# main_module_0_1.net
KiCad netlist of a schematic drawn in EAGLE
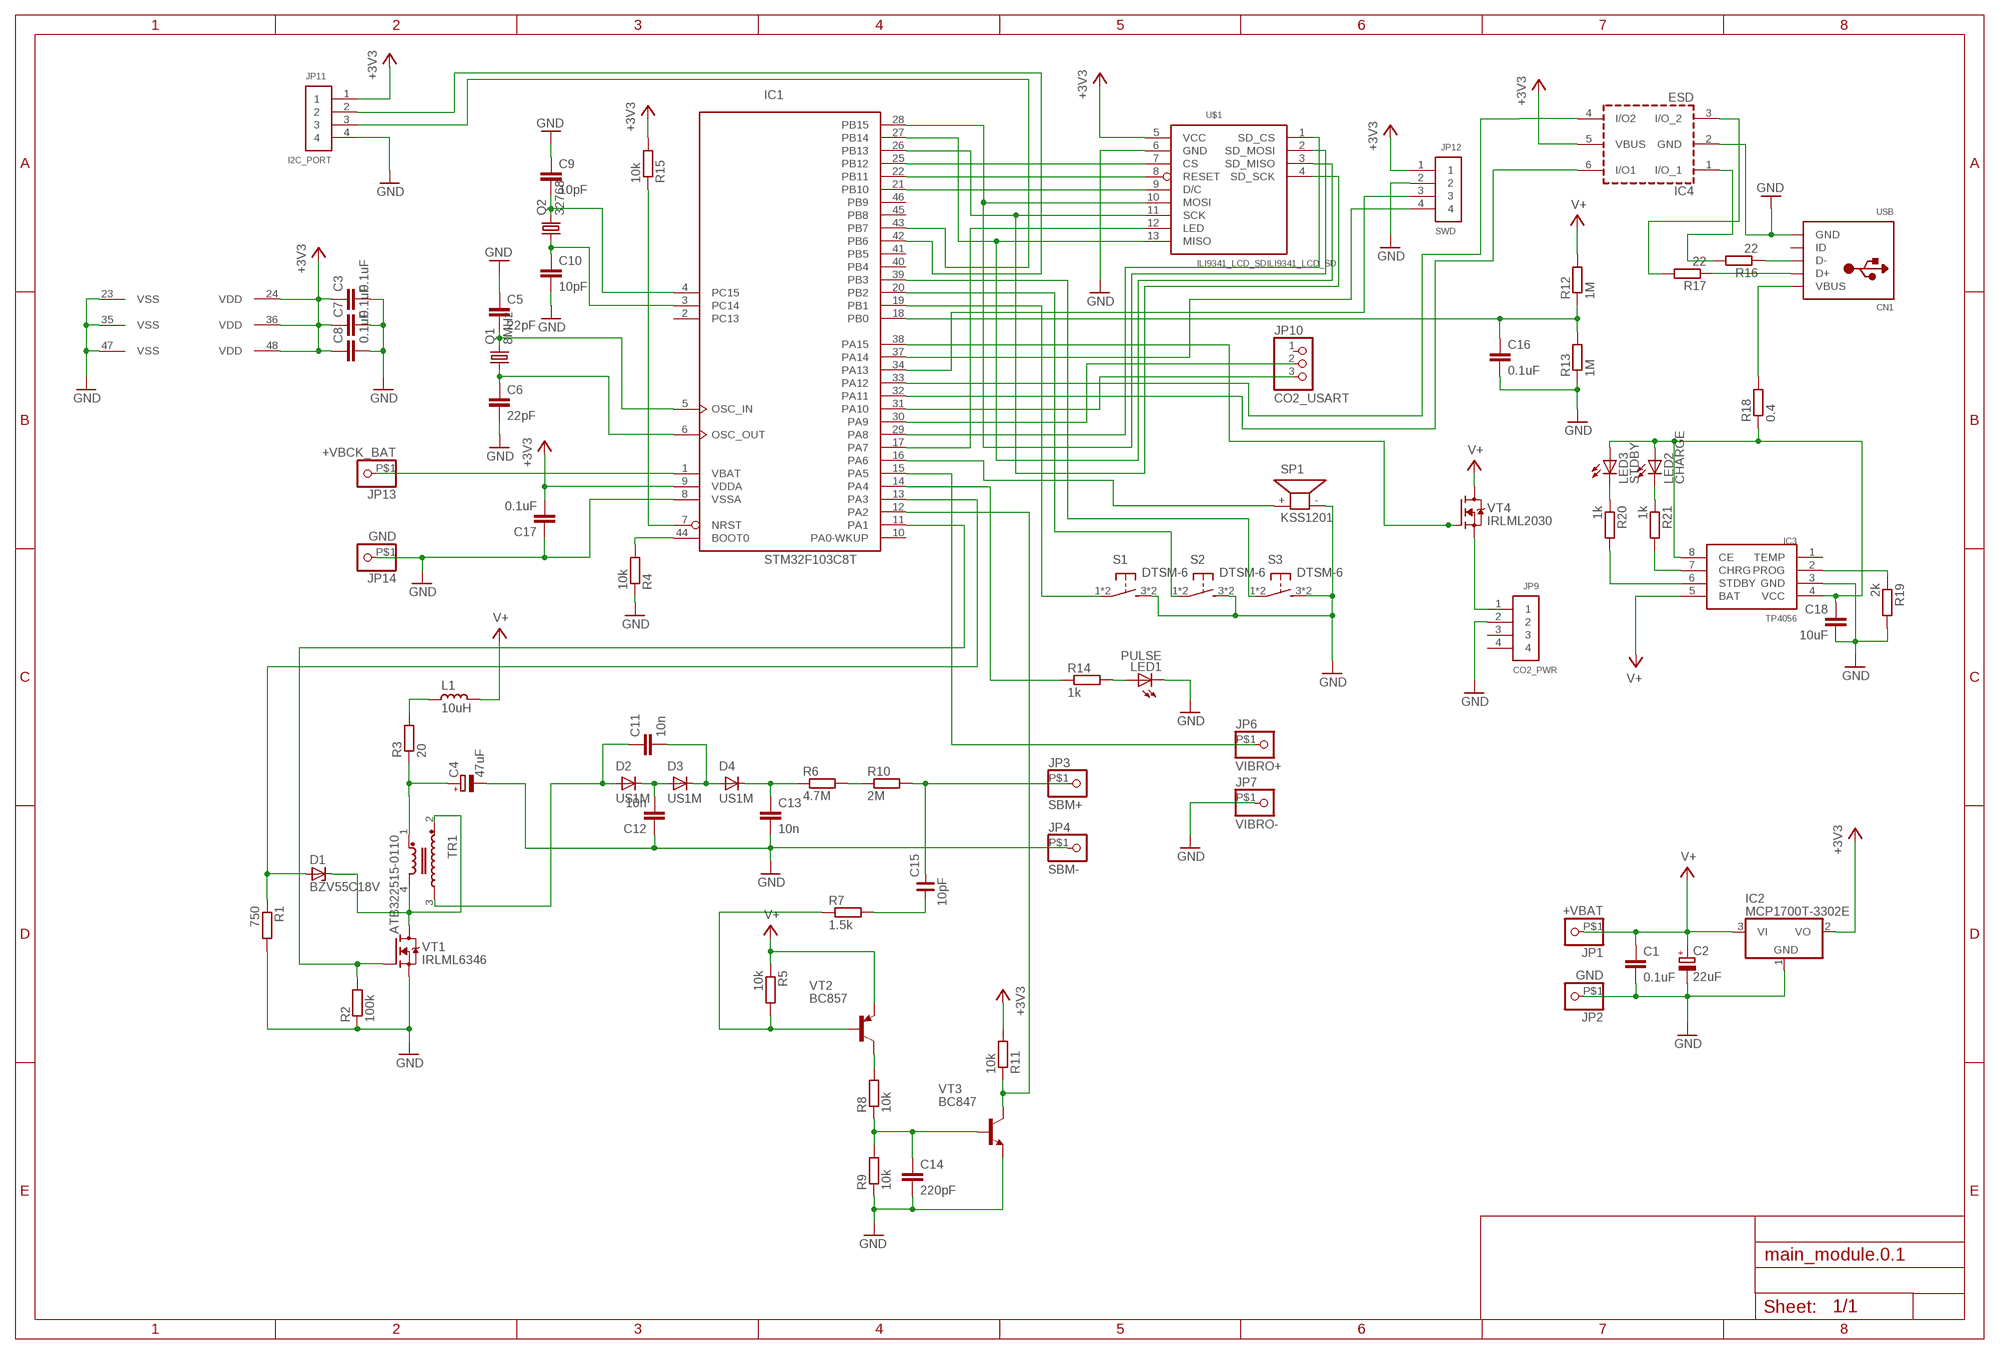
[diagram p0: schematic, sheet 1]

(export (version "E")
  (design (tool "Eeschema 10.0.6"))
  (components
    (comp (ref "C1")
      (value "0.1uF")
      (footprint "eagle-import:C0805")
      (libsource (lib "eagle-import") (part "C-EUC0805"))
    )
    (comp (ref "C2")
      (value "22uF")
      (footprint "eagle-import:C_6032-28R")
      (libsource (lib "eagle-import") (part "CPOL-EUC/6032-28R"))
    )
    (comp (ref "C3")
      (value "0.1uF")
      (footprint "eagle-import:C0805")
      (libsource (lib "eagle-import") (part "C-EUC0805"))
    )
    (comp (ref "C4")
      (value "47uF")
      (footprint "eagle-import:C_6032-28R")
      (libsource (lib "eagle-import") (part "CPOL-EUC/6032-28R"))
    )
    (comp (ref "C5")
      (value "22pF")
      (footprint "eagle-import:C0805")
      (libsource (lib "eagle-import") (part "C-EUC0805"))
    )
    (comp (ref "C6")
      (value "22pF")
      (footprint "eagle-import:C0805")
      (libsource (lib "eagle-import") (part "C-EUC0805"))
    )
    (comp (ref "C7")
      (value "0.1uF")
      (footprint "eagle-import:C0805")
      (libsource (lib "eagle-import") (part "C-EUC0805"))
    )
    (comp (ref "C8")
      (value "0.1uF")
      (footprint "eagle-import:C0805")
      (libsource (lib "eagle-import") (part "C-EUC0805"))
    )
    (comp (ref "C9")
      (value "10pF")
      (footprint "eagle-import:C0805")
      (libsource (lib "eagle-import") (part "C-EUC0805"))
    )
    (comp (ref "C10")
      (value "10pF")
      (footprint "eagle-import:C0805")
      (libsource (lib "eagle-import") (part "C-EUC0805"))
    )
    (comp (ref "C11")
      (value "10n")
      (footprint "eagle-import:C1206")
      (libsource (lib "eagle-import") (part "C-EUC1206"))
    )
    (comp (ref "C12")
      (value "10n")
      (footprint "eagle-import:C1206")
      (libsource (lib "eagle-import") (part "C-EUC1206"))
    )
    (comp (ref "C13")
      (value "10n")
      (footprint "eagle-import:C1206")
      (libsource (lib "eagle-import") (part "C-EUC1206"))
    )
    (comp (ref "C14")
      (value "220pF")
      (footprint "eagle-import:C0805")
      (libsource (lib "eagle-import") (part "C-EUC0805"))
    )
    (comp (ref "C15")
      (value "10pF")
      (footprint "eagle-import:C1206")
      (libsource (lib "eagle-import") (part "C_1206"))
    )
    (comp (ref "C16")
      (value "0.1uF")
      (footprint "eagle-import:C0805")
      (libsource (lib "eagle-import") (part "C-EUC0805"))
    )
    (comp (ref "C17")
      (value "0.1uF")
      (footprint "eagle-import:C0805")
      (libsource (lib "eagle-import") (part "C-EUC0805"))
    )
    (comp (ref "C18")
      (value "10uF")
      (footprint "eagle-import:C0805")
      (libsource (lib "eagle-import") (part "C-EUC0805"))
    )
    (comp (ref "CN1")
      (value "USB")
      (footprint "eagle-import:USB-MINIB")
      (libsource (lib "eagle-import") (part "USBMINIB"))
    )
    (comp (ref "D1")
      (value "BZV55C18V")
      (footprint "eagle-import:SOD80C")
      (libsource (lib "eagle-import") (part "ZENER-DIODESOD80C"))
    )
    (comp (ref "D2")
      (value "US1M")
      (footprint "eagle-import:SMA-DO214AC")
      (libsource (lib "eagle-import") (part "GF1"))
    )
    (comp (ref "D3")
      (value "US1M")
      (footprint "eagle-import:SMA-DO214AC")
      (libsource (lib "eagle-import") (part "GF1"))
    )
    (comp (ref "D4")
      (value "US1M")
      (footprint "eagle-import:SMA-DO214AC")
      (libsource (lib "eagle-import") (part "GF1"))
    )
    (comp (ref "IC1")
      (value "STM32F103C8T")
      (footprint "eagle-import:LQFP48")
      (libsource (lib "eagle-import") (part "STM32F103CT8"))
    )
    (comp (ref "IC2")
      (value "MCP1700T-3302E")
      (footprint "eagle-import:SOT23")
      (libsource (lib "eagle-import") (part "MCP1703CB"))
    )
    (comp (ref "IC3")
      (value "TP4056")
      (footprint "eagle-import:SOP-8")
      (libsource (lib "eagle-import") (part "TP4056"))
    )
    (comp (ref "IC4")
      (value "ESD")
      (footprint "eagle-import:SOT-23-6L")
      (libsource (lib "eagle-import") (part "USBLC6-2SC6"))
    )
    (comp (ref "JP1")
      (value "+VBAT")
      (footprint "eagle-import:1X1-BIGPOGO")
      (libsource (lib "eagle-import") (part "PINHD-1X1-BIGPOGO"))
    )
    (comp (ref "JP2")
      (value "GND")
      (footprint "eagle-import:1X1-BIGPOGO")
      (libsource (lib "eagle-import") (part "PINHD-1X1-BIGPOGO"))
    )
    (comp (ref "JP3")
      (value "SBM+")
      (footprint "eagle-import:1X1-BIGPOGO")
      (libsource (lib "eagle-import") (part "PINHD-1X1-BIGPOGO"))
    )
    (comp (ref "JP4")
      (value "SBM-")
      (footprint "eagle-import:1X1-BIGPOGO")
      (libsource (lib "eagle-import") (part "PINHD-1X1-BIGPOGO"))
    )
    (comp (ref "JP6")
      (value "VIBRO+")
      (footprint "eagle-import:1X1-BIGPOGO")
      (libsource (lib "eagle-import") (part "PINHD-1X1-BIGPOGO"))
    )
    (comp (ref "JP7")
      (value "VIBRO-")
      (footprint "eagle-import:1X1-BIGPOGO")
      (libsource (lib "eagle-import") (part "PINHD-1X1-BIGPOGO"))
    )
    (comp (ref "JP9")
      (value "CO2_PWR")
      (footprint "eagle-import:1X04-BIG")
      (libsource (lib "eagle-import") (part "1X4-BIG"))
    )
    (comp (ref "JP10")
      (value "CO2_USART")
      (footprint "eagle-import:1X03")
      (libsource (lib "eagle-import") (part "PINHD-1X3"))
    )
    (comp (ref "JP11")
      (value "I2C_PORT")
      (footprint "eagle-import:1X04-BIG")
      (libsource (lib "eagle-import") (part "1X4-BIG"))
    )
    (comp (ref "JP12")
      (value "SWD")
      (footprint "eagle-import:1X04-BIG")
      (libsource (lib "eagle-import") (part "1X4-BIG"))
    )
    (comp (ref "JP13")
      (value "+VBCK_BAT")
      (footprint "eagle-import:1X1-BIGPOGO")
      (libsource (lib "eagle-import") (part "PINHD-1X1-BIGPOGO"))
    )
    (comp (ref "JP14")
      (value "GND")
      (footprint "eagle-import:1X1-BIGPOGO")
      (libsource (lib "eagle-import") (part "PINHD-1X1-BIGPOGO"))
    )
    (comp (ref "L1")
      (value "10uH")
      (footprint "eagle-import:L0805")
      (libsource (lib "eagle-import") (part "L_0805"))
    )
    (comp (ref "LED1")
      (value "PULSE")
      (footprint "eagle-import:LED3MM")
      (libsource (lib "eagle-import") (part "LED3MM"))
    )
    (comp (ref "LED2")
      (value "CHARGE")
      (footprint "eagle-import:CHIP-LED0805")
      (libsource (lib "eagle-import") (part "led_LEDCHIP-LED0805"))
    )
    (comp (ref "LED3")
      (value "STDBY")
      (footprint "eagle-import:CHIP-LED0805")
      (libsource (lib "eagle-import") (part "led_LEDCHIP-LED0805"))
    )
    (comp (ref "Q1")
      (value "8MHz")
      (footprint "eagle-import:HC49_S")
      (libsource (lib "eagle-import") (part "CRYSTALHC49S"))
    )
    (comp (ref "Q2")
      (value "32768")
      (footprint "eagle-import:HC49_S")
      (libsource (lib "eagle-import") (part "CRYSTALHC49S"))
    )
    (comp (ref "R1")
      (value "750")
      (footprint "eagle-import:M0805")
      (libsource (lib "eagle-import") (part "R-EU_M0805"))
    )
    (comp (ref "R2")
      (value "100k")
      (footprint "eagle-import:M0805")
      (libsource (lib "eagle-import") (part "R-EU_M0805"))
    )
    (comp (ref "R3")
      (value "20")
      (footprint "eagle-import:M0805")
      (libsource (lib "eagle-import") (part "R-EU_M0805"))
    )
    (comp (ref "R4")
      (value "10k")
      (footprint "eagle-import:M0805")
      (libsource (lib "eagle-import") (part "R-EU_M0805"))
    )
    (comp (ref "R5")
      (value "10k")
      (footprint "eagle-import:M0805")
      (libsource (lib "eagle-import") (part "R-EU_M0805"))
    )
    (comp (ref "R6")
      (value "4.7M")
      (footprint "eagle-import:M0805")
      (libsource (lib "eagle-import") (part "R-EU_M0805"))
    )
    (comp (ref "R7")
      (value "1.5k")
      (footprint "eagle-import:M0805")
      (libsource (lib "eagle-import") (part "R-EU_M0805"))
    )
    (comp (ref "R8")
      (value "10k")
      (footprint "eagle-import:M0805")
      (libsource (lib "eagle-import") (part "R-EU_M0805"))
    )
    (comp (ref "R9")
      (value "10k")
      (footprint "eagle-import:M0805")
      (libsource (lib "eagle-import") (part "R-EU_M0805"))
    )
    (comp (ref "R10")
      (value "2M")
      (footprint "eagle-import:M0805")
      (libsource (lib "eagle-import") (part "R-EU_M0805"))
    )
    (comp (ref "R11")
      (value "10k")
      (footprint "eagle-import:M0805")
      (libsource (lib "eagle-import") (part "R-EU_M0805"))
    )
    (comp (ref "R12")
      (value "1M")
      (footprint "eagle-import:M0805")
      (libsource (lib "eagle-import") (part "R-EU_M0805"))
    )
    (comp (ref "R13")
      (value "1M")
      (footprint "eagle-import:M0805")
      (libsource (lib "eagle-import") (part "R-EU_M0805"))
    )
    (comp (ref "R14")
      (value "1k")
      (footprint "eagle-import:M0805")
      (libsource (lib "eagle-import") (part "R-EU_M0805"))
    )
    (comp (ref "R15")
      (value "10k")
      (footprint "eagle-import:M0805")
      (libsource (lib "eagle-import") (part "R-EU_M0805"))
    )
    (comp (ref "R16")
      (value "22")
      (footprint "eagle-import:M0805")
      (libsource (lib "eagle-import") (part "R-EU_M0805"))
    )
    (comp (ref "R17")
      (value "22")
      (footprint "eagle-import:M0805")
      (libsource (lib "eagle-import") (part "R-EU_M0805"))
    )
    (comp (ref "R18")
      (value "0.4")
      (footprint "eagle-import:M1206")
      (libsource (lib "eagle-import") (part "R-EU_M1206"))
    )
    (comp (ref "R19")
      (value "2k")
      (footprint "eagle-import:M0805")
      (libsource (lib "eagle-import") (part "R-EU_M0805"))
    )
    (comp (ref "R20")
      (value "1k")
      (footprint "eagle-import:M0805")
      (libsource (lib "eagle-import") (part "R-EU_M0805"))
    )
    (comp (ref "R21")
      (value "1k")
      (footprint "eagle-import:M0805")
      (libsource (lib "eagle-import") (part "R-EU_M0805"))
    )
    (comp (ref "S1")
      (value "DTSM-6")
      (footprint "eagle-import:DTSM-6")
      (libsource (lib "eagle-import") (part "DTSM-6"))
    )
    (comp (ref "S2")
      (value "DTSM-6")
      (footprint "eagle-import:DTSM-6")
      (libsource (lib "eagle-import") (part "DTSM-6"))
    )
    (comp (ref "S3")
      (value "DTSM-6")
      (footprint "eagle-import:DTSM-6")
      (libsource (lib "eagle-import") (part "DTSM-6"))
    )
    (comp (ref "SP1")
      (value "KSS1201")
      (footprint "eagle-import:KSS1201")
      (libsource (lib "eagle-import") (part "KSS1201"))
    )
    (comp (ref "TR1")
      (value "ATB322515-0110")
      (footprint "eagle-import:ATB3225")
      (libsource (lib "eagle-import") (part "ATB3225"))
    )
    (comp (ref "U$1")
      (value "ILI9341_LCD_SDILI9341_LCD_SD")
      (footprint "eagle-import:ILI9341_LCD_SD")
      (libsource (lib "eagle-import") (part "ILI9341_LCD_SDILI9341_LCD_SD"))
    )
    (comp (ref "VT1")
      (value "IRLML6346")
      (footprint "eagle-import:SOT23")
      (libsource (lib "eagle-import") (part "MOSFET-N-SOT23"))
    )
    (comp (ref "VT2")
      (value "BC857")
      (footprint "eagle-import:SOT23-BCE")
      (libsource (lib "eagle-import") (part "-PNP-SOT23-BCE"))
    )
    (comp (ref "VT3")
      (value "BC847")
      (footprint "eagle-import:SOT23")
      (libsource (lib "eagle-import") (part "BC847"))
    )
    (comp (ref "VT4")
      (value "IRLML2030")
      (footprint "eagle-import:SOT23")
      (libsource (lib "eagle-import") (part "MOSFET-N-SOT23"))
    )
  )
  (nets
    (net (code "1") (name "+3V3") (class "Default")
      (node (ref "C17") (pin "2") (pinfunction "2_2") (pintype "passive"))
      (node (ref "C3") (pin "1") (pinfunction "1_1") (pintype "passive"))
      (node (ref "C7") (pin "1") (pinfunction "1_1") (pintype "passive"))
      (node (ref "C8") (pin "1") (pinfunction "1_1") (pintype "passive"))
      (node (ref "IC1") (pin "24") (pinfunction "VDD_24") (pintype "power_in"))
      (node (ref "IC1") (pin "36") (pinfunction "VDD_36") (pintype "power_in"))
      (node (ref "IC1") (pin "48") (pinfunction "VDD_48") (pintype "power_in"))
      (node (ref "IC1") (pin "9") (pinfunction "VDDA_9") (pintype "power_in"))
      (node (ref "IC2") (pin "2") (pinfunction "VO_2") (pintype "passive"))
      (node (ref "IC4") (pin "5") (pinfunction "VBUS_5") (pintype "bidirectional"))
      (node (ref "JP11") (pin "1") (pinfunction "1_1") (pintype "bidirectional"))
      (node (ref "JP12") (pin "1") (pinfunction "1_1") (pintype "bidirectional"))
      (node (ref "R11") (pin "2") (pinfunction "2_2") (pintype "passive"))
      (node (ref "R15") (pin "2") (pinfunction "2_2") (pintype "passive"))
      (node (ref "U$1") (pin "5") (pinfunction "VCC_5") (pintype "power_in"))
    )
    (net (code "2") (name "GND") (class "Default")
      (node (ref "C1") (pin "2") (pinfunction "2_2") (pintype "passive"))
      (node (ref "C10") (pin "2") (pinfunction "2_2") (pintype "passive"))
      (node (ref "C12") (pin "1") (pinfunction "1_1") (pintype "passive"))
      (node (ref "C13") (pin "2") (pinfunction "2_2") (pintype "passive"))
      (node (ref "C14") (pin "2") (pinfunction "2_2") (pintype "passive"))
      (node (ref "C16") (pin "2") (pinfunction "2_2") (pintype "passive"))
      (node (ref "C17") (pin "1") (pinfunction "1_1") (pintype "passive"))
      (node (ref "C18") (pin "2") (pinfunction "2_2") (pintype "passive"))
      (node (ref "C2") (pin "-") (pinfunction "-_-") (pintype "passive"))
      (node (ref "C3") (pin "2") (pinfunction "2_2") (pintype "passive"))
      (node (ref "C4") (pin "-") (pinfunction "-_-") (pintype "passive"))
      (node (ref "C5") (pin "1") (pinfunction "1_1") (pintype "passive"))
      (node (ref "C6") (pin "2") (pinfunction "2_2") (pintype "passive"))
      (node (ref "C7") (pin "2") (pinfunction "2_2") (pintype "passive"))
      (node (ref "C8") (pin "2") (pinfunction "2_2") (pintype "passive"))
      (node (ref "C9") (pin "1") (pinfunction "1_1") (pintype "passive"))
      (node (ref "CN1") (pin "GND") (pinfunction "GND_GND") (pintype "power_in"))
      (node (ref "IC1") (pin "23") (pinfunction "VSS_23") (pintype "power_in"))
      (node (ref "IC1") (pin "35") (pinfunction "VSS_35") (pintype "power_in"))
      (node (ref "IC1") (pin "47") (pinfunction "VSS_47") (pintype "power_in"))
      (node (ref "IC1") (pin "8") (pinfunction "VSSA_8") (pintype "power_in"))
      (node (ref "IC2") (pin "1") (pinfunction "GND_1") (pintype "passive"))
      (node (ref "IC3") (pin "3") (pinfunction "GND_3") (pintype "bidirectional"))
      (node (ref "IC4") (pin "2") (pinfunction "GND_2") (pintype "bidirectional"))
      (node (ref "JP11") (pin "4") (pinfunction "4_4") (pintype "bidirectional"))
      (node (ref "JP12") (pin "2") (pinfunction "2_2") (pintype "bidirectional"))
      (node (ref "JP14") (pin "P$1") (pinfunction "1_P$1") (pintype "passive"))
      (node (ref "JP2") (pin "P$1") (pinfunction "1_P$1") (pintype "passive"))
      (node (ref "JP4") (pin "P$1") (pinfunction "1_P$1") (pintype "passive"))
      (node (ref "JP7") (pin "P$1") (pinfunction "1_P$1") (pintype "passive"))
      (node (ref "JP9") (pin "2") (pinfunction "2_2") (pintype "bidirectional"))
      (node (ref "LED1") (pin "K") (pinfunction "C_K") (pintype "passive"))
      (node (ref "R1") (pin "2") (pinfunction "2_2") (pintype "passive"))
      (node (ref "R13") (pin "1") (pinfunction "1_1") (pintype "passive"))
      (node (ref "R19") (pin "2") (pinfunction "2_2") (pintype "passive"))
      (node (ref "R2") (pin "1") (pinfunction "1_1") (pintype "passive"))
      (node (ref "R4") (pin "1") (pinfunction "1_1") (pintype "passive"))
      (node (ref "R9") (pin "1") (pinfunction "1_1") (pintype "passive"))
      (node (ref "S1") (pin "3") (pinfunction "3_3") (pintype "passive"))
      (node (ref "S1") (pin "4") (pinfunction "3_4") (pintype "passive"))
      (node (ref "S2") (pin "3") (pinfunction "3_3") (pintype "passive"))
      (node (ref "S2") (pin "4") (pinfunction "3_4") (pintype "passive"))
      (node (ref "S3") (pin "3") (pinfunction "3_3") (pintype "passive"))
      (node (ref "S3") (pin "4") (pinfunction "3_4") (pintype "passive"))
      (node (ref "SP1") (pin "-") (pinfunction "2_-") (pintype "passive"))
      (node (ref "U$1") (pin "6") (pinfunction "GND_6") (pintype "power_in"))
      (node (ref "VT1") (pin "2") (pinfunction "S_2") (pintype "passive"))
      (node (ref "VT3") (pin "2") (pinfunction "E_2") (pintype "passive"))
    )
    (net (code "3") (name "Net-(C4-Pad+)") (class "Default")
      (node (ref "C4") (pin "+") (pinfunction "+_+") (pintype "passive"))
      (node (ref "R3") (pin "1") (pinfunction "1_1") (pintype "passive"))
      (node (ref "TR1") (pin "1") (pinfunction "1_1") (pintype "passive"))
    )
    (net (code "4") (name "Net-(C11-Pad1)") (class "Default")
      (node (ref "C11") (pin "1") (pinfunction "1_1") (pintype "passive"))
      (node (ref "D2") (pin "A") (pinfunction "A_A") (pintype "passive"))
      (node (ref "TR1") (pin "3") (pinfunction "3_3") (pintype "passive"))
    )
    (net (code "5") (name "Net-(C15-Pad1)") (class "Default")
      (node (ref "C15") (pin "1") (pinfunction "1_1") (pintype "passive"))
      (node (ref "R7") (pin "2") (pinfunction "2_2") (pintype "passive"))
    )
    (net (code "6") (name "Net-(CN1-PadD+)") (class "Default")
      (node (ref "CN1") (pin "D+") (pinfunction "D+_D+") (pintype "bidirectional"))
      (node (ref "R17") (pin "1") (pinfunction "1_1") (pintype "passive"))
    )
    (net (code "7") (name "Net-(CN1-PadD-)") (class "Default")
      (node (ref "CN1") (pin "D-") (pinfunction "D-_D-") (pintype "bidirectional"))
      (node (ref "R16") (pin "1") (pinfunction "1_1") (pintype "passive"))
    )
    (net (code "8") (name "Net-(CN1-PadVBUS)") (class "Default")
      (node (ref "CN1") (pin "VBUS") (pinfunction "VBUS_VBUS") (pintype "power_in"))
      (node (ref "R18") (pin "2") (pinfunction "2_2") (pintype "passive"))
    )
    (net (code "9") (name "Net-(D2-C)") (class "Default")
      (node (ref "C12") (pin "2") (pinfunction "2_2") (pintype "passive"))
      (node (ref "D2") (pin "K") (pinfunction "C_K") (pintype "passive"))
      (node (ref "D3") (pin "A") (pinfunction "A_A") (pintype "passive"))
    )
    (net (code "10") (name "Net-(D3-C)") (class "Default")
      (node (ref "C11") (pin "2") (pinfunction "2_2") (pintype "passive"))
      (node (ref "D3") (pin "K") (pinfunction "C_K") (pintype "passive"))
      (node (ref "D4") (pin "A") (pinfunction "A_A") (pintype "passive"))
    )
    (net (code "11") (name "Net-(D4-C)") (class "Default")
      (node (ref "C13") (pin "1") (pinfunction "1_1") (pintype "passive"))
      (node (ref "D4") (pin "K") (pinfunction "C_K") (pintype "passive"))
      (node (ref "R6") (pin "1") (pinfunction "1_1") (pintype "passive"))
    )
    (net (code "12") (name "Net-(IC1A-BOOT0)") (class "Default")
      (node (ref "IC1") (pin "44") (pinfunction "BOOT0_44") (pintype "input"))
      (node (ref "R4") (pin "2") (pinfunction "2_2") (pintype "passive"))
    )
    (net (code "13") (name "Net-(IC1A-NRST)") (class "Default")
      (node (ref "IC1") (pin "7") (pinfunction "NRST_7") (pintype "bidirectional"))
      (node (ref "R15") (pin "1") (pinfunction "1_1") (pintype "passive"))
    )
    (net (code "14") (name "Net-(IC1A-OSC_IN)") (class "Default")
      (node (ref "C5") (pin "2") (pinfunction "2_2") (pintype "passive"))
      (node (ref "IC1") (pin "5") (pinfunction "OSC_IN_5") (pintype "bidirectional"))
      (node (ref "Q1") (pin "2") (pinfunction "2_2") (pintype "passive"))
    )
    (net (code "15") (name "Net-(IC1A-OSC_OUT)") (class "Default")
      (node (ref "C6") (pin "1") (pinfunction "1_1") (pintype "passive"))
      (node (ref "IC1") (pin "6") (pinfunction "OSC_OUT_6") (pintype "bidirectional"))
      (node (ref "Q1") (pin "1") (pinfunction "1_1") (pintype "passive"))
    )
    (net (code "16") (name "Net-(IC1A-PA1)") (class "Default")
      (node (ref "IC1") (pin "11") (pinfunction "PA1_11") (pintype "bidirectional"))
      (node (ref "R2") (pin "2") (pinfunction "2_2") (pintype "passive"))
      (node (ref "VT1") (pin "1") (pinfunction "G_1") (pintype "passive"))
    )
    (net (code "17") (name "Net-(IC1A-PA2)") (class "Default")
      (node (ref "IC1") (pin "12") (pinfunction "PA2_12") (pintype "bidirectional"))
      (node (ref "R11") (pin "1") (pinfunction "1_1") (pintype "passive"))
      (node (ref "VT3") (pin "3") (pinfunction "C_3") (pintype "passive"))
    )
    (net (code "18") (name "Net-(IC1A-PA3)") (class "Default")
      (node (ref "D1") (pin "A") (pinfunction "A_A") (pintype "passive"))
      (node (ref "IC1") (pin "13") (pinfunction "PA3_13") (pintype "bidirectional"))
      (node (ref "R1") (pin "1") (pinfunction "1_1") (pintype "passive"))
    )
    (net (code "19") (name "Net-(IC1A-PA4)") (class "Default")
      (node (ref "IC1") (pin "14") (pinfunction "PA4_14") (pintype "bidirectional"))
      (node (ref "R14") (pin "1") (pinfunction "1_1") (pintype "passive"))
    )
    (net (code "20") (name "Net-(IC1A-PA5)") (class "Default")
      (node (ref "IC1") (pin "15") (pinfunction "PA5_15") (pintype "bidirectional"))
      (node (ref "JP6") (pin "P$1") (pinfunction "1_P$1") (pintype "passive"))
    )
    (net (code "21") (name "Net-(IC1A-PA6)") (class "Default")
      (node (ref "IC1") (pin "16") (pinfunction "PA6_16") (pintype "bidirectional"))
      (node (ref "SP1") (pin "+") (pinfunction "1_+") (pintype "passive"))
    )
    (net (code "22") (name "Net-(IC1A-PA7)") (class "Default")
      (node (ref "IC1") (pin "17") (pinfunction "PA7_17") (pintype "bidirectional"))
      (node (ref "U$1") (pin "12") (pinfunction "LED_12") (pintype "input"))
    )
    (net (code "23") (name "Net-(IC1A-PA8)") (class "Default")
      (node (ref "IC1") (pin "29") (pinfunction "PA8_29") (pintype "bidirectional"))
      (node (ref "U$1") (pin "1") (pinfunction "SD_CS_1") (pintype "input"))
    )
    (net (code "24") (name "Net-(IC1A-PA9)") (class "Default")
      (node (ref "IC1") (pin "30") (pinfunction "PA9_30") (pintype "bidirectional"))
      (node (ref "JP10") (pin "2") (pinfunction "2_2") (pintype "passive"))
    )
    (net (code "25") (name "Net-(IC1A-PA10)") (class "Default")
      (node (ref "IC1") (pin "31") (pinfunction "PA10_31") (pintype "bidirectional"))
      (node (ref "JP10") (pin "3") (pinfunction "3_3") (pintype "passive"))
    )
    (net (code "26") (name "Net-(IC1A-PA11)") (class "Default")
      (node (ref "IC1") (pin "32") (pinfunction "PA11_32") (pintype "bidirectional"))
      (node (ref "IC4") (pin "6") (pinfunction "I/O1_6") (pintype "bidirectional"))
    )
    (net (code "27") (name "Net-(IC1A-PA12)") (class "Default")
      (node (ref "IC1") (pin "33") (pinfunction "PA12_33") (pintype "bidirectional"))
      (node (ref "IC4") (pin "4") (pinfunction "I/O2_4") (pintype "bidirectional"))
    )
    (net (code "28") (name "Net-(IC1A-PA13)") (class "Default")
      (node (ref "IC1") (pin "34") (pinfunction "PA13_34") (pintype "bidirectional"))
      (node (ref "JP12") (pin "3") (pinfunction "3_3") (pintype "bidirectional"))
    )
    (net (code "29") (name "Net-(IC1A-PA14)") (class "Default")
      (node (ref "IC1") (pin "37") (pinfunction "PA14_37") (pintype "bidirectional"))
      (node (ref "JP12") (pin "4") (pinfunction "4_4") (pintype "bidirectional"))
    )
    (net (code "30") (name "Net-(IC1A-PA15)") (class "Default")
      (node (ref "IC1") (pin "38") (pinfunction "PA15_38") (pintype "bidirectional"))
      (node (ref "VT4") (pin "1") (pinfunction "G_1") (pintype "passive"))
    )
    (net (code "31") (name "Net-(IC1A-PB0)") (class "Default")
      (node (ref "C16") (pin "1") (pinfunction "1_1") (pintype "passive"))
      (node (ref "IC1") (pin "18") (pinfunction "PB0_18") (pintype "bidirectional"))
      (node (ref "R12") (pin "1") (pinfunction "1_1") (pintype "passive"))
      (node (ref "R13") (pin "2") (pinfunction "2_2") (pintype "passive"))
    )
    (net (code "32") (name "Net-(IC1A-PB1)") (class "Default")
      (node (ref "IC1") (pin "19") (pinfunction "PB1_19") (pintype "bidirectional"))
      (node (ref "S1") (pin "1") (pinfunction "1_1") (pintype "passive"))
      (node (ref "S1") (pin "2") (pinfunction "1_2") (pintype "passive"))
    )
    (net (code "33") (name "Net-(IC1A-PB2)") (class "Default")
      (node (ref "IC1") (pin "20") (pinfunction "PB2_20") (pintype "bidirectional"))
      (node (ref "S2") (pin "1") (pinfunction "1_1") (pintype "passive"))
      (node (ref "S2") (pin "2") (pinfunction "1_2") (pintype "passive"))
    )
    (net (code "34") (name "Net-(IC1A-PB3)") (class "Default")
      (node (ref "IC1") (pin "39") (pinfunction "PB3_39") (pintype "bidirectional"))
      (node (ref "S3") (pin "1") (pinfunction "1_1") (pintype "passive"))
      (node (ref "S3") (pin "2") (pinfunction "1_2") (pintype "passive"))
    )
    (net (code "35") (name "Net-(IC1A-PB6)") (class "Default")
      (node (ref "IC1") (pin "42") (pinfunction "PB6_42") (pintype "bidirectional"))
      (node (ref "JP11") (pin "2") (pinfunction "2_2") (pintype "bidirectional"))
    )
    (net (code "36") (name "Net-(IC1A-PB7)") (class "Default")
      (node (ref "IC1") (pin "43") (pinfunction "PB7_43") (pintype "bidirectional"))
      (node (ref "JP11") (pin "3") (pinfunction "3_3") (pintype "bidirectional"))
    )
    (net (code "37") (name "Net-(IC1A-PB10)") (class "Default")
      (node (ref "IC1") (pin "21") (pinfunction "PB10_21") (pintype "bidirectional"))
      (node (ref "U$1") (pin "9") (pinfunction "D/C_9") (pintype "input"))
    )
    (net (code "38") (name "Net-(IC1A-PB11)") (class "Default")
      (node (ref "IC1") (pin "22") (pinfunction "PB11_22") (pintype "bidirectional"))
      (node (ref "U$1") (pin "8") (pinfunction "RESET_8") (pintype "input"))
    )
    (net (code "39") (name "Net-(IC1A-PB12)") (class "Default")
      (node (ref "IC1") (pin "25") (pinfunction "PB12_25") (pintype "bidirectional"))
      (node (ref "U$1") (pin "7") (pinfunction "CS_7") (pintype "input"))
    )
    (net (code "40") (name "Net-(IC1A-PB13)") (class "Default")
      (node (ref "IC1") (pin "26") (pinfunction "PB13_26") (pintype "bidirectional"))
      (node (ref "U$1") (pin "11") (pinfunction "SCK_11") (pintype "input"))
      (node (ref "U$1") (pin "4") (pinfunction "SD_SCK_4") (pintype "input"))
    )
    (net (code "41") (name "Net-(IC1A-PB14)") (class "Default")
      (node (ref "IC1") (pin "27") (pinfunction "PB14_27") (pintype "bidirectional"))
      (node (ref "U$1") (pin "13") (pinfunction "MISO_13") (pintype "bidirectional"))
      (node (ref "U$1") (pin "3") (pinfunction "SD_MISO_3") (pintype "bidirectional"))
    )
    (net (code "42") (name "Net-(IC1A-PB15)") (class "Default")
      (node (ref "IC1") (pin "28") (pinfunction "PB15_28") (pintype "bidirectional"))
      (node (ref "U$1") (pin "10") (pinfunction "MOSI_10") (pintype "bidirectional"))
      (node (ref "U$1") (pin "2") (pinfunction "SD_MOSI_2") (pintype "bidirectional"))
    )
    (net (code "43") (name "Net-(IC1A-PC14)") (class "Default")
      (node (ref "C10") (pin "1") (pinfunction "1_1") (pintype "passive"))
      (node (ref "IC1") (pin "3") (pinfunction "PC14_3") (pintype "bidirectional"))
      (node (ref "Q2") (pin "1") (pinfunction "1_1") (pintype "passive"))
    )
    (net (code "44") (name "Net-(IC1A-PC15)") (class "Default")
      (node (ref "C9") (pin "2") (pinfunction "2_2") (pintype "passive"))
      (node (ref "IC1") (pin "4") (pinfunction "PC15_4") (pintype "bidirectional"))
      (node (ref "Q2") (pin "2") (pinfunction "2_2") (pintype "passive"))
    )
    (net (code "45") (name "Net-(IC1A-VBAT)") (class "Default")
      (node (ref "IC1") (pin "1") (pinfunction "VBAT_1") (pintype "power_in"))
      (node (ref "JP13") (pin "P$1") (pinfunction "1_P$1") (pintype "passive"))
    )
    (net (code "46") (name "Net-(IC3-CE)") (class "Default")
      (node (ref "C18") (pin "1") (pinfunction "1_1") (pintype "passive"))
      (node (ref "IC3") (pin "4") (pinfunction "VCC_4") (pintype "bidirectional"))
      (node (ref "IC3") (pin "8") (pinfunction "CE_8") (pintype "bidirectional"))
      (node (ref "LED2") (pin "A") (pinfunction "A_A") (pintype "passive"))
      (node (ref "LED3") (pin "A") (pinfunction "A_A") (pintype "passive"))
      (node (ref "R18") (pin "1") (pinfunction "1_1") (pintype "passive"))
    )
    (net (code "47") (name "Net-(IC3-CHRG)") (class "Default")
      (node (ref "IC3") (pin "7") (pinfunction "CHRG_7") (pintype "bidirectional"))
      (node (ref "R21") (pin "2") (pinfunction "2_2") (pintype "passive"))
    )
    (net (code "48") (name "Net-(IC3-PROG)") (class "Default")
      (node (ref "IC3") (pin "2") (pinfunction "PROG_2") (pintype "bidirectional"))
      (node (ref "R19") (pin "1") (pinfunction "1_1") (pintype "passive"))
    )
    (net (code "49") (name "Net-(IC3-STDBY)") (class "Default")
      (node (ref "IC3") (pin "6") (pinfunction "STDBY_6") (pintype "bidirectional"))
      (node (ref "R20") (pin "2") (pinfunction "2_2") (pintype "passive"))
    )
    (net (code "50") (name "Net-(IC4-I{slash}O_1)") (class "Default")
      (node (ref "IC4") (pin "1") (pinfunction "I/O_1_1") (pintype "bidirectional"))
      (node (ref "R16") (pin "2") (pinfunction "2_2") (pintype "passive"))
    )
    (net (code "51") (name "Net-(IC4-I{slash}O_2)") (class "Default")
      (node (ref "IC4") (pin "3") (pinfunction "I/O_2_3") (pintype "bidirectional"))
      (node (ref "R17") (pin "2") (pinfunction "2_2") (pintype "passive"))
    )
    (net (code "52") (name "Net-(JP3-1)") (class "Default")
      (node (ref "C15") (pin "2") (pinfunction "2_2") (pintype "passive"))
      (node (ref "JP3") (pin "P$1") (pinfunction "1_P$1") (pintype "passive"))
      (node (ref "R10") (pin "2") (pinfunction "2_2") (pintype "passive"))
    )
    (net (code "53") (name "Net-(L1-Pad2)") (class "Default")
      (node (ref "L1") (pin "2") (pinfunction "2_2") (pintype "passive"))
      (node (ref "R3") (pin "2") (pinfunction "2_2") (pintype "passive"))
    )
    (net (code "54") (name "Net-(LED1-PadA)") (class "Default")
      (node (ref "LED1") (pin "A") (pinfunction "A_A") (pintype "passive"))
      (node (ref "R14") (pin "2") (pinfunction "2_2") (pintype "passive"))
    )
    (net (code "55") (name "Net-(LED2-PadC)") (class "Default")
      (node (ref "LED2") (pin "C") (pinfunction "C_C") (pintype "passive"))
      (node (ref "R21") (pin "1") (pinfunction "1_1") (pintype "passive"))
    )
    (net (code "56") (name "Net-(LED3-PadC)") (class "Default")
      (node (ref "LED3") (pin "C") (pinfunction "C_C") (pintype "passive"))
      (node (ref "R20") (pin "1") (pinfunction "1_1") (pintype "passive"))
    )
    (net (code "57") (name "Net-(R5-Pad2)") (class "Default")
      (node (ref "R5") (pin "2") (pinfunction "2_2") (pintype "passive"))
      (node (ref "R7") (pin "1") (pinfunction "1_1") (pintype "passive"))
      (node (ref "VT2") (pin "B") (pinfunction "B_B") (pintype "passive"))
    )
    (net (code "58") (name "Net-(R8-Pad2)") (class "Default")
      (node (ref "R8") (pin "2") (pinfunction "2_2") (pintype "passive"))
      (node (ref "VT2") (pin "C") (pinfunction "C_C") (pintype "passive"))
    )
    (net (code "59") (name "Net-(R10-Pad1)") (class "Default")
      (node (ref "R10") (pin "1") (pinfunction "1_1") (pintype "passive"))
      (node (ref "R6") (pin "2") (pinfunction "2_2") (pintype "passive"))
    )
    (net (code "60") (name "Net-(VT1-D)") (class "Default")
      (node (ref "D1") (pin "C") (pinfunction "C_C") (pintype "passive"))
      (node (ref "TR1") (pin "2") (pinfunction "2_2") (pintype "passive"))
      (node (ref "TR1") (pin "4") (pinfunction "4_4") (pintype "passive"))
      (node (ref "VT1") (pin "3") (pinfunction "D_3") (pintype "passive"))
    )
    (net (code "61") (name "Net-(VT3-B)") (class "Default")
      (node (ref "C14") (pin "1") (pinfunction "1_1") (pintype "passive"))
      (node (ref "R8") (pin "1") (pinfunction "1_1") (pintype "passive"))
      (node (ref "R9") (pin "2") (pinfunction "2_2") (pintype "passive"))
      (node (ref "VT3") (pin "1") (pinfunction "B_1") (pintype "passive"))
    )
    (net (code "62") (name "Net-(VT4-S)") (class "Default")
      (node (ref "JP9") (pin "1") (pinfunction "1_1") (pintype "bidirectional"))
      (node (ref "VT4") (pin "2") (pinfunction "S_2") (pintype "passive"))
    )
    (net (code "63") (name "V+") (class "Default")
      (node (ref "C1") (pin "1") (pinfunction "1_1") (pintype "passive"))
      (node (ref "C2") (pin "+") (pinfunction "+_+") (pintype "passive"))
      (node (ref "IC2") (pin "3") (pinfunction "VI_3") (pintype "input"))
      (node (ref "IC3") (pin "5") (pinfunction "BAT_5") (pintype "bidirectional"))
      (node (ref "JP1") (pin "P$1") (pinfunction "1_P$1") (pintype "passive"))
      (node (ref "L1") (pin "1") (pinfunction "1_1") (pintype "passive"))
      (node (ref "R12") (pin "2") (pinfunction "2_2") (pintype "passive"))
      (node (ref "R5") (pin "1") (pinfunction "1_1") (pintype "passive"))
      (node (ref "VT2") (pin "E") (pinfunction "E_E") (pintype "passive"))
      (node (ref "VT4") (pin "3") (pinfunction "D_3") (pintype "passive"))
    )
    (net (code "64") (name "unconnected-(CN1-PadID)") (class "Default")
      (node (ref "CN1") (pin "ID") (pinfunction "ID_ID") (pintype "bidirectional"))
    )
    (net (code "65") (name "unconnected-(IC1A-PA0-WKUP-Pad10)") (class "Default")
      (node (ref "IC1") (pin "10") (pinfunction "PA0-WKUP_10") (pintype "bidirectional"))
    )
    (net (code "66") (name "unconnected-(IC1A-PB4-Pad40)") (class "Default")
      (node (ref "IC1") (pin "40") (pinfunction "PB4_40") (pintype "bidirectional"))
    )
    (net (code "67") (name "unconnected-(IC1A-PB5-Pad41)") (class "Default")
      (node (ref "IC1") (pin "41") (pinfunction "PB5_41") (pintype "bidirectional"))
    )
    (net (code "68") (name "unconnected-(IC1A-PB8-Pad45)") (class "Default")
      (node (ref "IC1") (pin "45") (pinfunction "PB8_45") (pintype "bidirectional"))
    )
    (net (code "69") (name "unconnected-(IC1A-PB9-Pad46)") (class "Default")
      (node (ref "IC1") (pin "46") (pinfunction "PB9_46") (pintype "bidirectional"))
    )
    (net (code "70") (name "unconnected-(IC1A-PC13-Pad2)") (class "Default")
      (node (ref "IC1") (pin "2") (pinfunction "PC13_2") (pintype "bidirectional"))
    )
    (net (code "71") (name "unconnected-(IC3-TEMP-Pad1)") (class "Default")
      (node (ref "IC3") (pin "1") (pinfunction "TEMP_1") (pintype "bidirectional"))
    )
    (net (code "72") (name "unconnected-(JP9-Pad3)") (class "Default")
      (node (ref "JP9") (pin "3") (pinfunction "3_3") (pintype "bidirectional"))
    )
    (net (code "73") (name "unconnected-(JP9-Pad4)") (class "Default")
      (node (ref "JP9") (pin "4") (pinfunction "4_4") (pintype "bidirectional"))
    )
    (net (code "74") (name "unconnected-(JP10-Pad1)") (class "Default")
      (node (ref "JP10") (pin "1") (pinfunction "1_1") (pintype "passive"))
    )
  )
)
